# Sheet1.net
KiCad netlist of a schematic drawn in Altium Designer
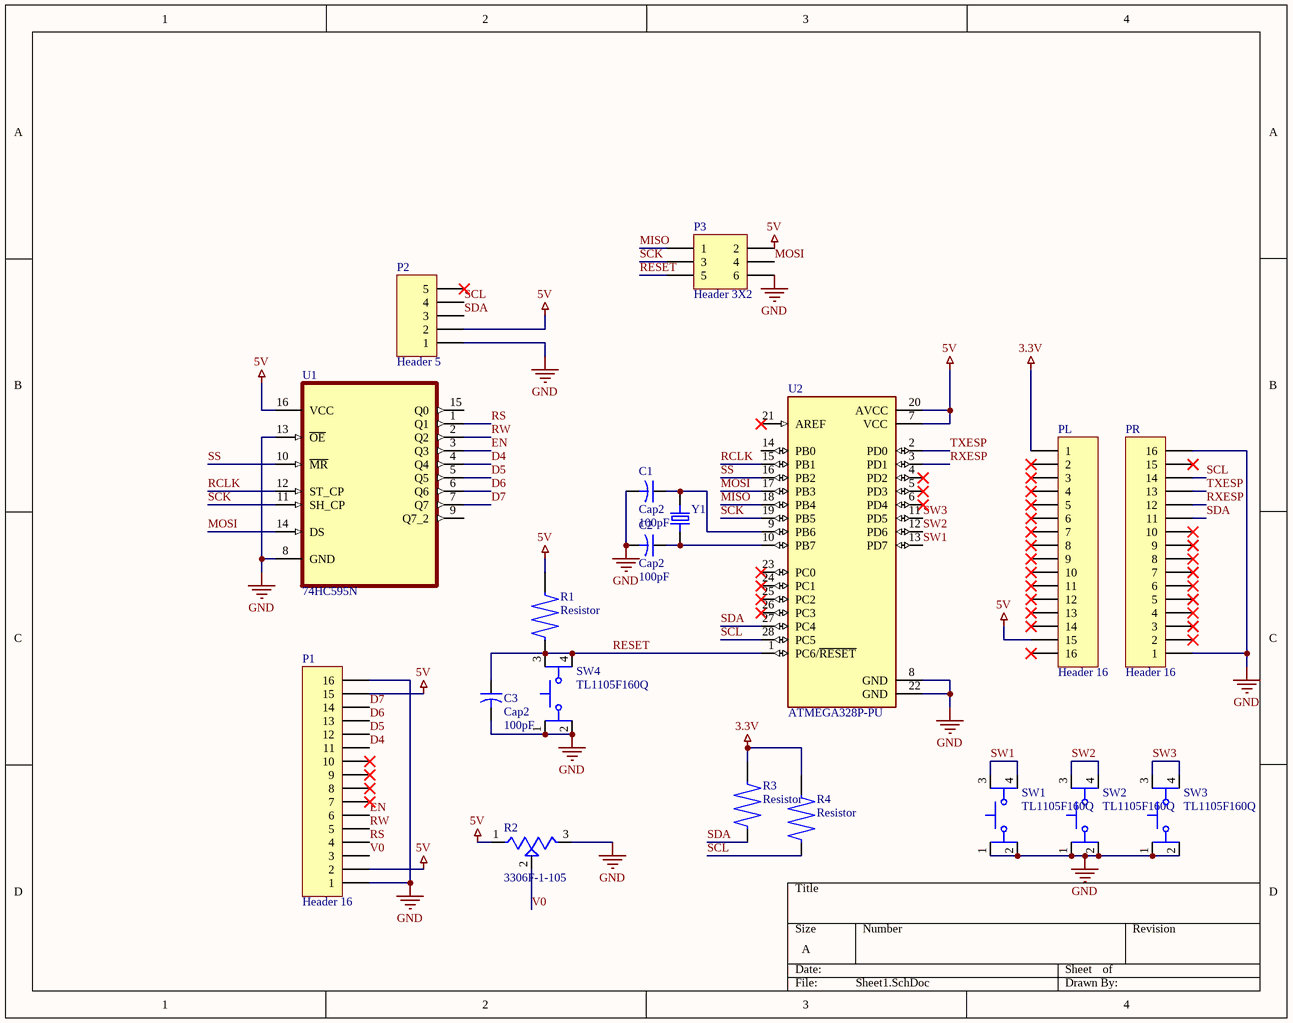
[diagram p0: Sheet1.SchDoc]

(export (version "E")
  (design (tool "Eeschema 10.0.6"))
  (components
    (comp (ref "C1")
      (value "Cap2")
      (footprint "CAPR5-4X5")
      (description "Capacitor")
      (fields (field (name "ALTIUM_VALUE") "100pF") (field (name "PUBLISHER") "Altium Limited"))
      (libsource (lib "Miscellaneous Devices") (part "Cap2"))
    )
    (comp (ref "C2")
      (value "Cap2")
      (footprint "CAPR5-4X5")
      (description "Capacitor")
      (fields (field (name "ALTIUM_VALUE") "100pF") (field (name "PUBLISHER") "Altium Limited"))
      (libsource (lib "Miscellaneous Devices") (part "Cap2"))
    )
    (comp (ref "C3")
      (value "Cap2")
      (footprint "CAPR5-4X5")
      (description "Capacitor")
      (fields (field (name "ALTIUM_VALUE") "100pF") (field (name "PUBLISHER") "Altium Limited"))
      (libsource (lib "Miscellaneous Devices") (part "Cap2"))
    )
    (comp (ref "P1")
      (value "Header 16")
      (footprint "HDR1X16")
      (description "Header, 16-Pin")
      (fields (field (name "PUBLISHER") "Altium Limited"))
      (libsource (lib "Miscellaneous Connectors") (part "Header 16"))
    )
    (comp (ref "P2")
      (value "Header 5")
      (footprint "HDR1X5")
      (description "Header, 5-Pin")
      (fields (field (name "PUBLISHER") "Altium Limited"))
      (libsource (lib "Miscellaneous Connectors") (part "Header 5"))
    )
    (comp (ref "P3")
      (value "Header 3X2")
      (footprint "HDR2X3")
      (description "Header, 3-Pin, Dual row")
      (fields (field (name "PUBLISHER") "Altium Limited"))
      (libsource (lib "Miscellaneous Connectors") (part "Header 3X2"))
    )
    (comp (ref "PL")
      (value "Header 16")
      (footprint "HDR1X16")
      (description "Header, 16-Pin")
      (fields (field (name "PUBLISHER") "Altium Limited"))
      (libsource (lib "") (part "Header 16_1"))
    )
    (comp (ref "PR")
      (value "Header 16")
      (footprint "HDR1X16")
      (description "Header, 16-Pin")
      (fields (field (name "PUBLISHER") "Altium Limited"))
      (libsource (lib "Miscellaneous Connectors") (part "Header 16"))
    )
    (comp (ref "R1")
      (value "Resistor")
      (footprint "StandingAxial")
      (libsource (lib "MClock") (part "Resistor"))
    )
    (comp (ref "R2")
      (value "3306F-1-105")
      (footprint "TRIM_3306F-1-105")
      (description "1 MOhms 0.2W, 1/5W PC Pins Through Hole Trimmer Potentiometer Cermet 1 Turn Top Adjustment")
      (libsource (lib "MClock") (part "3306F-1-105"))
    )
    (comp (ref "R3")
      (value "Resistor")
      (footprint "StandingAxial")
      (libsource (lib "MClock") (part "Resistor"))
    )
    (comp (ref "R4")
      (value "Resistor")
      (footprint "StandingAxial")
      (libsource (lib "MClock") (part "Resistor"))
    )
    (comp (ref "SW1")
      (value "TL1105F160Q")
      (footprint "SW_TL1105F160Q")
      (libsource (lib "MClock") (part "TL1105F160Q"))
    )
    (comp (ref "SW2")
      (value "TL1105F160Q")
      (footprint "SW_TL1105F160Q")
      (libsource (lib "MClock") (part "TL1105F160Q"))
    )
    (comp (ref "SW3")
      (value "TL1105F160Q")
      (footprint "SW_TL1105F160Q")
      (libsource (lib "MClock") (part "TL1105F160Q"))
    )
    (comp (ref "SW4")
      (value "TL1105F160Q")
      (footprint "SW_TL1105F160Q")
      (libsource (lib "MClock") (part "TL1105F160Q"))
    )
    (comp (ref "U1")
      (value "74HC595N")
      (footprint "DIP254P762X420-16")
      (description "Shift Shift Register 1 Element 8 Bit 16-DIP")
      (libsource (lib "MClock") (part "74HC595N"))
    )
    (comp (ref "U2")
      (value "ATMEGA328P-PU")
      (footprint "DIP794W46P254L2967H457Q28B")
      (description "ATmega Series 20 MHz 32 KB Flash 2 KB SRAM 8-Bit Microcontroller - DIP-28")
      (libsource (lib "MClock") (part "ATMEGA328P-PU"))
    )
    (comp (ref "Y1")
      (value "ECS-160-S-4")
      (footprint "XTAL_ECS-160-20-4X")
      (description "16MHz Â±30ppm Crystal Series 40 Ohms HC-49/US")
      (libsource (lib "MClock") (part "ECS-160-S-4"))
    )
  )
  (nets
    (net (code "1") (name "/D4") (class "Default")
      (node (ref "P1") (pin "11") (pinfunction "11_11") (pintype "passive"))
      (node (ref "U1") (pin "4") (pinfunction "Q4_4") (pintype "output"))
    )
    (net (code "2") (name "/D5") (class "Default")
      (node (ref "P1") (pin "12") (pinfunction "12_12") (pintype "passive"))
      (node (ref "U1") (pin "5") (pinfunction "Q5_5") (pintype "output"))
    )
    (net (code "3") (name "/D6") (class "Default")
      (node (ref "P1") (pin "13") (pinfunction "13_13") (pintype "passive"))
      (node (ref "U1") (pin "6") (pinfunction "Q6_6") (pintype "output"))
    )
    (net (code "4") (name "/D7") (class "Default")
      (node (ref "P1") (pin "14") (pinfunction "14_14") (pintype "passive"))
      (node (ref "U1") (pin "7") (pinfunction "Q7_7") (pintype "output"))
    )
    (net (code "5") (name "/EN") (class "Default")
      (node (ref "P1") (pin "6") (pinfunction "6_6") (pintype "passive"))
      (node (ref "U1") (pin "3") (pinfunction "Q3_3") (pintype "output"))
    )
    (net (code "6") (name "/MISO") (class "Default")
      (node (ref "P3") (pin "1") (pinfunction "1_1") (pintype "passive"))
      (node (ref "U2") (pin "18") (pinfunction "PB4_18") (pintype "bidirectional"))
    )
    (net (code "7") (name "/MOSI") (class "Default")
      (node (ref "P3") (pin "4") (pinfunction "4_4") (pintype "passive"))
      (node (ref "U1") (pin "14") (pinfunction "DS_14") (pintype "input"))
      (node (ref "U2") (pin "17") (pinfunction "PB3_17") (pintype "bidirectional"))
    )
    (net (code "8") (name "/RCLK") (class "Default")
      (node (ref "U1") (pin "12") (pinfunction "ST_CP_12") (pintype "input"))
      (node (ref "U2") (pin "15") (pinfunction "PB1_15") (pintype "bidirectional"))
    )
    (net (code "9") (name "/RESET") (class "Default")
      (node (ref "C3") (pin "1") (pinfunction "1_1") (pintype "passive"))
      (node (ref "P3") (pin "5") (pinfunction "5_5") (pintype "passive"))
      (node (ref "R1") (pin "0") (pinfunction "0_0") (pintype "passive"))
      (node (ref "SW4") (pin "3") (pinfunction "3_3") (pintype "passive"))
      (node (ref "SW4") (pin "4") (pinfunction "4_4") (pintype "passive"))
      (node (ref "U2") (pin "1") (pinfunction "PC6/~{RESET}_1") (pintype "bidirectional"))
    )
    (net (code "10") (name "/RS") (class "Default")
      (node (ref "P1") (pin "4") (pinfunction "4_4") (pintype "passive"))
      (node (ref "U1") (pin "1") (pinfunction "Q1_1") (pintype "output"))
    )
    (net (code "11") (name "/RW") (class "Default")
      (node (ref "P1") (pin "5") (pinfunction "5_5") (pintype "passive"))
      (node (ref "U1") (pin "2") (pinfunction "Q2_2") (pintype "output"))
    )
    (net (code "12") (name "/RXESP") (class "Default")
      (node (ref "PR") (pin "12") (pinfunction "12_12") (pintype "passive"))
      (node (ref "U2") (pin "3") (pinfunction "PD1_3") (pintype "bidirectional"))
    )
    (net (code "13") (name "/SCK") (class "Default")
      (node (ref "P3") (pin "3") (pinfunction "3_3") (pintype "passive"))
      (node (ref "U1") (pin "11") (pinfunction "SH_CP_11") (pintype "input"))
      (node (ref "U2") (pin "19") (pinfunction "PB5_19") (pintype "bidirectional"))
    )
    (net (code "14") (name "/SCL") (class "Default")
      (node (ref "P2") (pin "4") (pinfunction "4_4") (pintype "passive"))
      (node (ref "PR") (pin "14") (pinfunction "14_14") (pintype "passive"))
      (node (ref "R4") (pin "0") (pinfunction "0_0") (pintype "passive"))
      (node (ref "U2") (pin "28") (pinfunction "PC5_28") (pintype "bidirectional"))
    )
    (net (code "15") (name "/SDA") (class "Default")
      (node (ref "P2") (pin "3") (pinfunction "3_3") (pintype "passive"))
      (node (ref "PR") (pin "11") (pinfunction "11_11") (pintype "passive"))
      (node (ref "R3") (pin "0") (pinfunction "0_0") (pintype "passive"))
      (node (ref "U2") (pin "27") (pinfunction "PC4_27") (pintype "bidirectional"))
    )
    (net (code "16") (name "/SS") (class "Default")
      (node (ref "U1") (pin "10") (pinfunction "~{MR}_10") (pintype "input"))
      (node (ref "U2") (pin "16") (pinfunction "PB2_16") (pintype "bidirectional"))
    )
    (net (code "17") (name "/SW1") (class "Default")
      (node (ref "SW1") (pin "3") (pinfunction "3_3") (pintype "passive"))
      (node (ref "SW1") (pin "4") (pinfunction "4_4") (pintype "passive"))
      (node (ref "U2") (pin "13") (pinfunction "PD7_13") (pintype "bidirectional"))
    )
    (net (code "18") (name "/SW2") (class "Default")
      (node (ref "SW2") (pin "3") (pinfunction "3_3") (pintype "passive"))
      (node (ref "SW2") (pin "4") (pinfunction "4_4") (pintype "passive"))
      (node (ref "U2") (pin "12") (pinfunction "PD6_12") (pintype "bidirectional"))
    )
    (net (code "19") (name "/SW3") (class "Default")
      (node (ref "SW3") (pin "3") (pinfunction "3_3") (pintype "passive"))
      (node (ref "SW3") (pin "4") (pinfunction "4_4") (pintype "passive"))
      (node (ref "U2") (pin "11") (pinfunction "PD5_11") (pintype "bidirectional"))
    )
    (net (code "20") (name "/TXESP") (class "Default")
      (node (ref "PR") (pin "13") (pinfunction "13_13") (pintype "passive"))
      (node (ref "U2") (pin "2") (pinfunction "PD0_2") (pintype "bidirectional"))
    )
    (net (code "21") (name "/V0") (class "Default")
      (node (ref "P1") (pin "3") (pinfunction "3_3") (pintype "passive"))
      (node (ref "R2") (pin "2") (pinfunction "WIPER_2") (pintype "passive"))
    )
    (net (code "22") (name "3.3V") (class "Default")
      (node (ref "PL") (pin "1") (pinfunction "1_1") (pintype "passive"))
      (node (ref "R3") (pin "1") (pinfunction "1_1") (pintype "passive"))
      (node (ref "R4") (pin "1") (pinfunction "1_1") (pintype "passive"))
    )
    (net (code "23") (name "5V") (class "Default")
      (node (ref "P1") (pin "15") (pinfunction "15_15") (pintype "passive"))
      (node (ref "P1") (pin "2") (pinfunction "2_2") (pintype "passive"))
      (node (ref "P2") (pin "2") (pinfunction "2_2") (pintype "passive"))
      (node (ref "P3") (pin "2") (pinfunction "2_2") (pintype "passive"))
      (node (ref "PL") (pin "15") (pinfunction "15_15") (pintype "passive"))
      (node (ref "R1") (pin "1") (pinfunction "1_1") (pintype "passive"))
      (node (ref "R2") (pin "1") (pinfunction "CCW_1") (pintype "passive"))
      (node (ref "U1") (pin "16") (pinfunction "VCC_16") (pintype "power_in"))
      (node (ref "U2") (pin "20") (pinfunction "AVCC_20") (pintype "power_in"))
      (node (ref "U2") (pin "7") (pinfunction "VCC_7") (pintype "power_in"))
    )
    (net (code "24") (name "GND") (class "Default")
      (node (ref "C1") (pin "2") (pinfunction "2_2") (pintype "passive"))
      (node (ref "C2") (pin "2") (pinfunction "2_2") (pintype "passive"))
      (node (ref "C3") (pin "2") (pinfunction "2_2") (pintype "passive"))
      (node (ref "P1") (pin "1") (pinfunction "1_1") (pintype "passive"))
      (node (ref "P1") (pin "16") (pinfunction "16_16") (pintype "passive"))
      (node (ref "P2") (pin "1") (pinfunction "1_1") (pintype "passive"))
      (node (ref "P3") (pin "6") (pinfunction "6_6") (pintype "passive"))
      (node (ref "PR") (pin "1") (pinfunction "1_1") (pintype "passive"))
      (node (ref "PR") (pin "16") (pinfunction "16_16") (pintype "passive"))
      (node (ref "R2") (pin "3") (pinfunction "CW_3") (pintype "passive"))
      (node (ref "SW1") (pin "1") (pinfunction "1_1") (pintype "passive"))
      (node (ref "SW1") (pin "2") (pinfunction "2_2") (pintype "passive"))
      (node (ref "SW2") (pin "1") (pinfunction "1_1") (pintype "passive"))
      (node (ref "SW2") (pin "2") (pinfunction "2_2") (pintype "passive"))
      (node (ref "SW3") (pin "1") (pinfunction "1_1") (pintype "passive"))
      (node (ref "SW3") (pin "2") (pinfunction "2_2") (pintype "passive"))
      (node (ref "SW4") (pin "1") (pinfunction "1_1") (pintype "passive"))
      (node (ref "SW4") (pin "2") (pinfunction "2_2") (pintype "passive"))
      (node (ref "U1") (pin "13") (pinfunction "~{OE}_13") (pintype "input"))
      (node (ref "U1") (pin "8") (pinfunction "GND_8") (pintype "passive"))
      (node (ref "U2") (pin "22") (pinfunction "GND_22") (pintype "power_in"))
      (node (ref "U2") (pin "8") (pinfunction "GND_8") (pintype "power_in"))
    )
    (net (code "25") (name "Net-(U2-PB6)") (class "Default")
      (node (ref "C1") (pin "1") (pinfunction "1_1") (pintype "passive"))
      (node (ref "U2") (pin "9") (pinfunction "PB6_9") (pintype "bidirectional"))
      (node (ref "Y1") (pin "2") (pinfunction "2_2") (pintype "passive"))
    )
    (net (code "26") (name "Net-(U2-PB7)") (class "Default")
      (node (ref "C2") (pin "1") (pinfunction "1_1") (pintype "passive"))
      (node (ref "U2") (pin "10") (pinfunction "PB7_10") (pintype "bidirectional"))
      (node (ref "Y1") (pin "1") (pinfunction "1_1") (pintype "passive"))
    )
    (net (code "27") (name "unconnected-(P1-Pad7)") (class "Default")
      (node (ref "P1") (pin "7") (pinfunction "7_7") (pintype "passive+no_connect"))
    )
    (net (code "28") (name "unconnected-(P1-Pad8)") (class "Default")
      (node (ref "P1") (pin "8") (pinfunction "8_8") (pintype "passive+no_connect"))
    )
    (net (code "29") (name "unconnected-(P1-Pad9)") (class "Default")
      (node (ref "P1") (pin "9") (pinfunction "9_9") (pintype "passive+no_connect"))
    )
    (net (code "30") (name "unconnected-(P1-Pad10)") (class "Default")
      (node (ref "P1") (pin "10") (pinfunction "10_10") (pintype "passive+no_connect"))
    )
    (net (code "31") (name "unconnected-(P2-Pad5)") (class "Default")
      (node (ref "P2") (pin "5") (pinfunction "5_5") (pintype "passive+no_connect"))
    )
    (net (code "32") (name "unconnected-(PL-Pad2)") (class "Default")
      (node (ref "PL") (pin "2") (pinfunction "2_2") (pintype "passive+no_connect"))
    )
    (net (code "33") (name "unconnected-(PL-Pad3)") (class "Default")
      (node (ref "PL") (pin "3") (pinfunction "3_3") (pintype "passive+no_connect"))
    )
    (net (code "34") (name "unconnected-(PL-Pad4)") (class "Default")
      (node (ref "PL") (pin "4") (pinfunction "4_4") (pintype "passive+no_connect"))
    )
    (net (code "35") (name "unconnected-(PL-Pad5)") (class "Default")
      (node (ref "PL") (pin "5") (pinfunction "5_5") (pintype "passive+no_connect"))
    )
    (net (code "36") (name "unconnected-(PL-Pad6)") (class "Default")
      (node (ref "PL") (pin "6") (pinfunction "6_6") (pintype "passive+no_connect"))
    )
    (net (code "37") (name "unconnected-(PL-Pad7)") (class "Default")
      (node (ref "PL") (pin "7") (pinfunction "7_7") (pintype "passive+no_connect"))
    )
    (net (code "38") (name "unconnected-(PL-Pad8)") (class "Default")
      (node (ref "PL") (pin "8") (pinfunction "8_8") (pintype "passive+no_connect"))
    )
    (net (code "39") (name "unconnected-(PL-Pad9)") (class "Default")
      (node (ref "PL") (pin "9") (pinfunction "9_9") (pintype "passive+no_connect"))
    )
    (net (code "40") (name "unconnected-(PL-Pad10)") (class "Default")
      (node (ref "PL") (pin "10") (pinfunction "10_10") (pintype "passive+no_connect"))
    )
    (net (code "41") (name "unconnected-(PL-Pad11)") (class "Default")
      (node (ref "PL") (pin "11") (pinfunction "11_11") (pintype "passive+no_connect"))
    )
    (net (code "42") (name "unconnected-(PL-Pad12)") (class "Default")
      (node (ref "PL") (pin "12") (pinfunction "12_12") (pintype "passive+no_connect"))
    )
    (net (code "43") (name "unconnected-(PL-Pad13)") (class "Default")
      (node (ref "PL") (pin "13") (pinfunction "13_13") (pintype "passive+no_connect"))
    )
    (net (code "44") (name "unconnected-(PL-Pad14)") (class "Default")
      (node (ref "PL") (pin "14") (pinfunction "14_14") (pintype "passive+no_connect"))
    )
    (net (code "45") (name "unconnected-(PL-Pad16)") (class "Default")
      (node (ref "PL") (pin "16") (pinfunction "16_16") (pintype "passive+no_connect"))
    )
    (net (code "46") (name "unconnected-(PR-Pad2)") (class "Default")
      (node (ref "PR") (pin "2") (pinfunction "2_2") (pintype "passive+no_connect"))
    )
    (net (code "47") (name "unconnected-(PR-Pad3)") (class "Default")
      (node (ref "PR") (pin "3") (pinfunction "3_3") (pintype "passive+no_connect"))
    )
    (net (code "48") (name "unconnected-(PR-Pad4)") (class "Default")
      (node (ref "PR") (pin "4") (pinfunction "4_4") (pintype "passive+no_connect"))
    )
    (net (code "49") (name "unconnected-(PR-Pad5)") (class "Default")
      (node (ref "PR") (pin "5") (pinfunction "5_5") (pintype "passive+no_connect"))
    )
    (net (code "50") (name "unconnected-(PR-Pad6)") (class "Default")
      (node (ref "PR") (pin "6") (pinfunction "6_6") (pintype "passive+no_connect"))
    )
    (net (code "51") (name "unconnected-(PR-Pad7)") (class "Default")
      (node (ref "PR") (pin "7") (pinfunction "7_7") (pintype "passive+no_connect"))
    )
    (net (code "52") (name "unconnected-(PR-Pad8)") (class "Default")
      (node (ref "PR") (pin "8") (pinfunction "8_8") (pintype "passive+no_connect"))
    )
    (net (code "53") (name "unconnected-(PR-Pad9)") (class "Default")
      (node (ref "PR") (pin "9") (pinfunction "9_9") (pintype "passive+no_connect"))
    )
    (net (code "54") (name "unconnected-(PR-Pad10)") (class "Default")
      (node (ref "PR") (pin "10") (pinfunction "10_10") (pintype "passive+no_connect"))
    )
    (net (code "55") (name "unconnected-(PR-Pad15)") (class "Default")
      (node (ref "PR") (pin "15") (pinfunction "15_15") (pintype "passive+no_connect"))
    )
    (net (code "56") (name "unconnected-(U1-Q0-Pad15)") (class "Default")
      (node (ref "U1") (pin "15") (pinfunction "Q0_15") (pintype "output"))
    )
    (net (code "57") (name "unconnected-(U1-Q7_2-Pad9)") (class "Default")
      (node (ref "U1") (pin "9") (pinfunction "Q7_2_9") (pintype "output"))
    )
    (net (code "58") (name "unconnected-(U2-AREF-Pad21)") (class "Default")
      (node (ref "U2") (pin "21") (pinfunction "AREF_21") (pintype "input+no_connect"))
    )
    (net (code "59") (name "unconnected-(U2-PB0-Pad14)") (class "Default")
      (node (ref "U2") (pin "14") (pinfunction "PB0_14") (pintype "bidirectional"))
    )
    (net (code "60") (name "unconnected-(U2-PC0-Pad23)") (class "Default")
      (node (ref "U2") (pin "23") (pinfunction "PC0_23") (pintype "bidirectional+no_connect"))
    )
    (net (code "61") (name "unconnected-(U2-PC1-Pad24)") (class "Default")
      (node (ref "U2") (pin "24") (pinfunction "PC1_24") (pintype "bidirectional+no_connect"))
    )
    (net (code "62") (name "unconnected-(U2-PC2-Pad25)") (class "Default")
      (node (ref "U2") (pin "25") (pinfunction "PC2_25") (pintype "bidirectional+no_connect"))
    )
    (net (code "63") (name "unconnected-(U2-PC3-Pad26)") (class "Default")
      (node (ref "U2") (pin "26") (pinfunction "PC3_26") (pintype "bidirectional+no_connect"))
    )
    (net (code "64") (name "unconnected-(U2-PD2-Pad4)") (class "Default")
      (node (ref "U2") (pin "4") (pinfunction "PD2_4") (pintype "bidirectional+no_connect"))
    )
    (net (code "65") (name "unconnected-(U2-PD3-Pad5)") (class "Default")
      (node (ref "U2") (pin "5") (pinfunction "PD3_5") (pintype "bidirectional+no_connect"))
    )
    (net (code "66") (name "unconnected-(U2-PD4-Pad6)") (class "Default")
      (node (ref "U2") (pin "6") (pinfunction "PD4_6") (pintype "bidirectional+no_connect"))
    )
  )
)
